# Opener.net
KiCad netlist of a schematic drawn in EAGLE
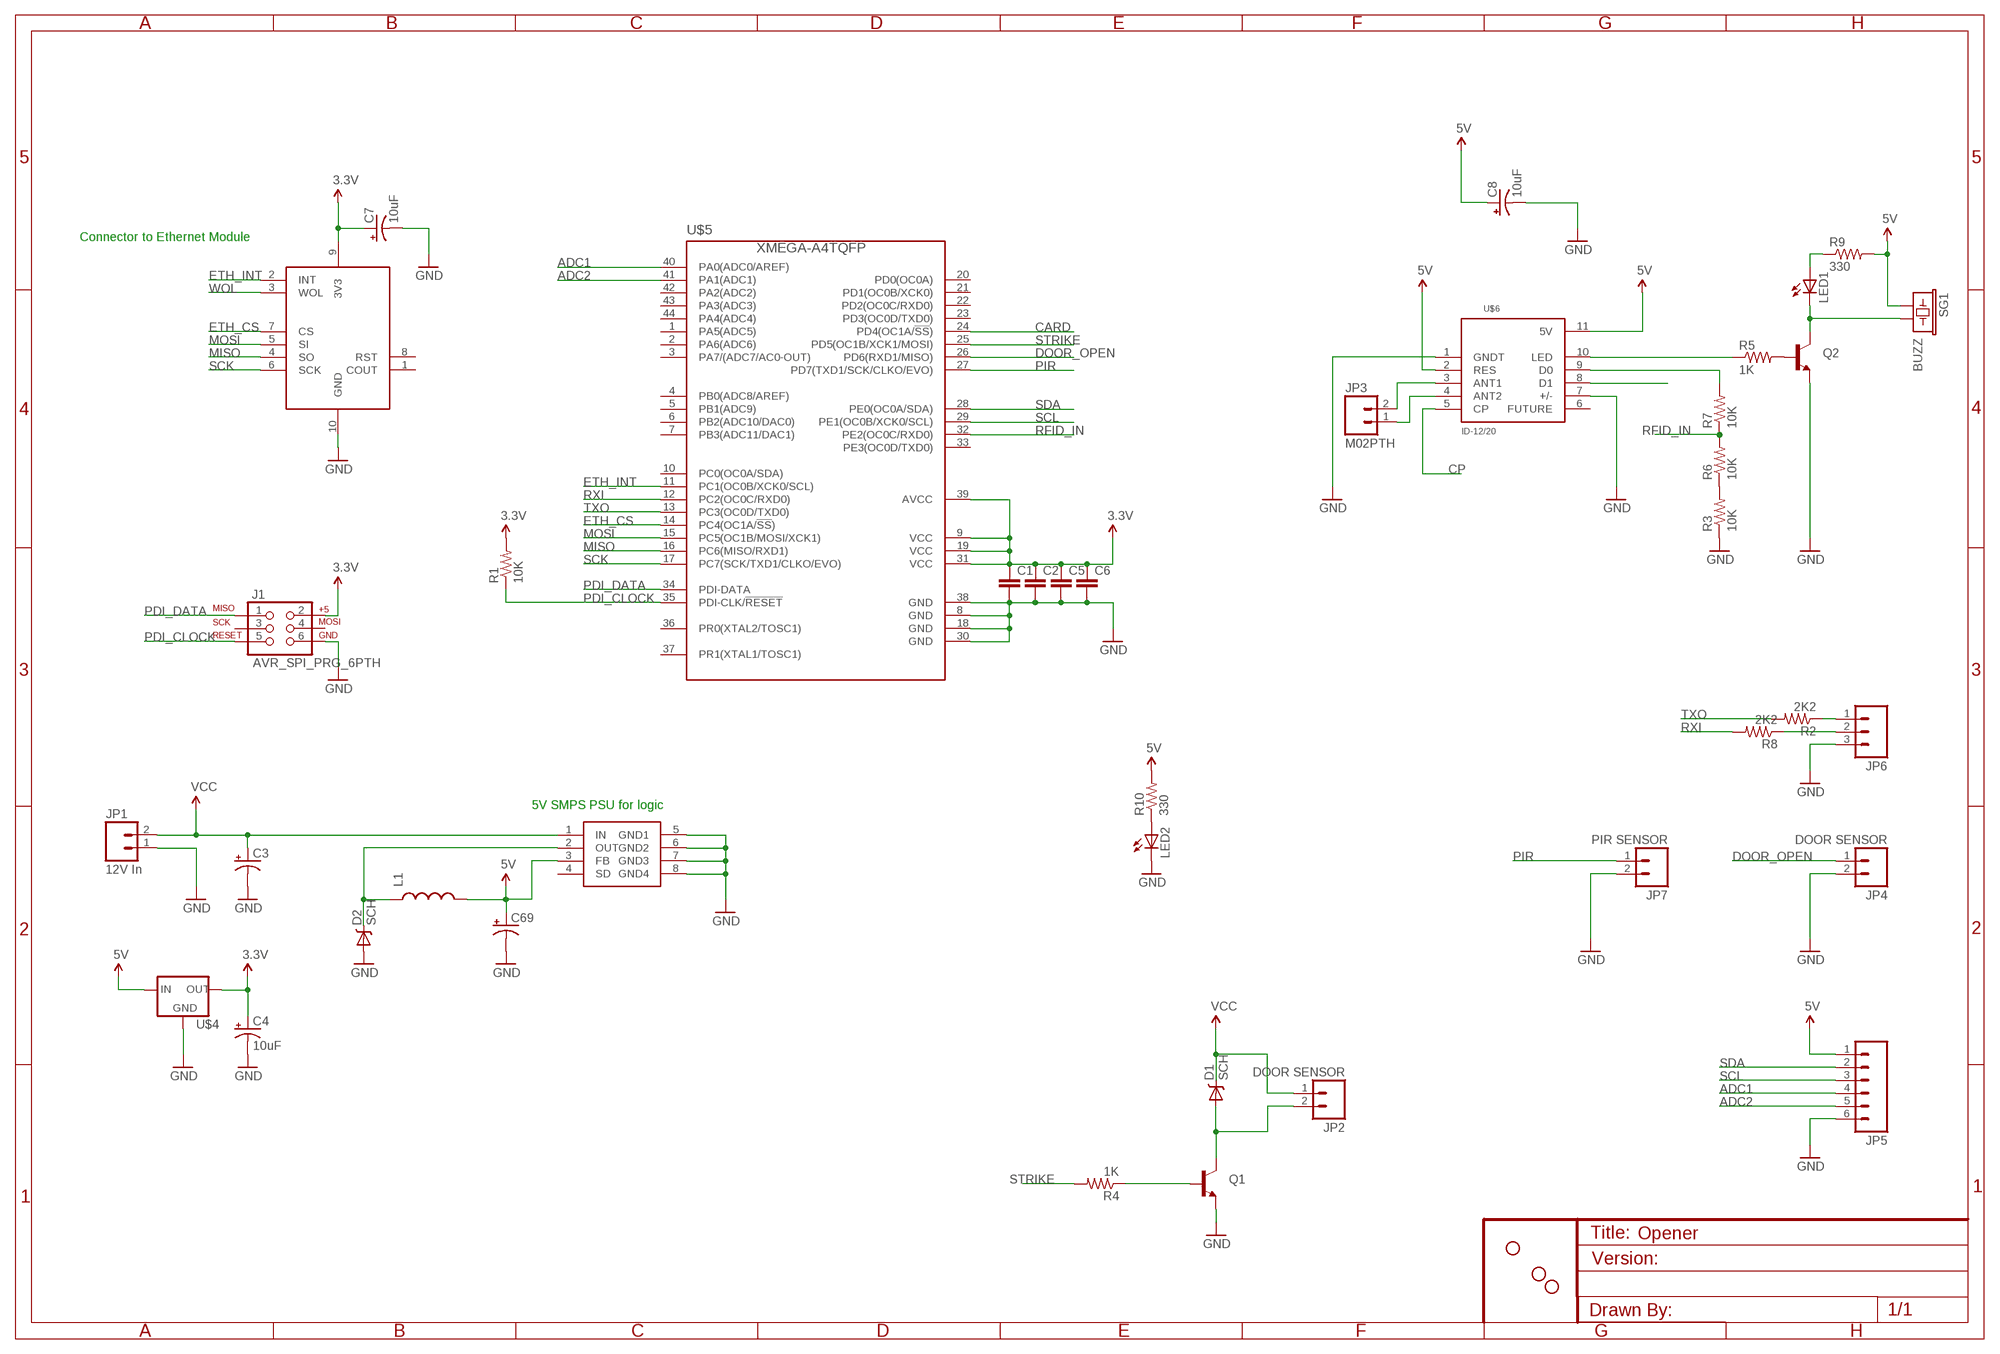
[diagram p0: schematic, sheet 1]

(export (version "E")
  (design (tool "Eeschema 10.0.6"))
  (components
    (comp (ref "C1")
      (value "CAP0603-CAP")
      (footprint "eagle-import:0603-CAP")
      (libsource (lib "eagle-import") (part "CAP0603-CAP"))
    )
    (comp (ref "C2")
      (value "CAP0603-CAP")
      (footprint "eagle-import:0603-CAP")
      (libsource (lib "eagle-import") (part "CAP0603-CAP"))
    )
    (comp (ref "C3")
      (value "CAP_POLPTH1")
      (footprint "eagle-import:CPOL-RADIAL-100UF-25V")
      (libsource (lib "eagle-import") (part "CAP_POLPTH1"))
    )
    (comp (ref "C4")
      (value "10uF")
      (footprint "eagle-import:EIA3216")
      (libsource (lib "eagle-import") (part "CAP_POL1206"))
    )
    (comp (ref "C5")
      (value "CAP0603-CAP")
      (footprint "eagle-import:0603-CAP")
      (libsource (lib "eagle-import") (part "CAP0603-CAP"))
    )
    (comp (ref "C6")
      (value "CAP0603-CAP")
      (footprint "eagle-import:0603-CAP")
      (libsource (lib "eagle-import") (part "CAP0603-CAP"))
    )
    (comp (ref "C7")
      (value "10uF")
      (footprint "eagle-import:EIA3216")
      (libsource (lib "eagle-import") (part "CAP_POL1206"))
    )
    (comp (ref "C8")
      (value "10uF")
      (footprint "eagle-import:EIA3216")
      (libsource (lib "eagle-import") (part "CAP_POL1206"))
    )
    (comp (ref "C69")
      (value "CAP_POLPTH1")
      (footprint "eagle-import:CPOL-RADIAL-100UF-25V")
      (libsource (lib "eagle-import") (part "CAP_POLPTH1"))
    )
    (comp (ref "D1")
      (value "SCH")
      (footprint "eagle-import:SMA-DIODE")
      (libsource (lib "eagle-import") (part "DIODE-SCHOTTKY_"))
    )
    (comp (ref "D2")
      (value "SCH")
      (footprint "eagle-import:SMA-DIODE")
      (libsource (lib "eagle-import") (part "DIODE-SCHOTTKY_"))
    )
    (comp (ref "J1")
      (value "AVR_SPI_PRG_6PTH")
      (footprint "eagle-import:2X3")
      (libsource (lib "eagle-import") (part "AVR_SPI_PRG_6PTH"))
    )
    (comp (ref "JP1")
      (value "12V In")
      (footprint "eagle-import:SCREWTERMINAL-3.5MM-2")
      (libsource (lib "eagle-import") (part "M023.5MM"))
    )
    (comp (ref "JP2")
      (value "DOOR SENSOR")
      (footprint "eagle-import:MOLEX-1X2")
      (libsource (lib "eagle-import") (part "M02POLAR"))
    )
    (comp (ref "JP3")
      (value "M02PTH")
      (footprint "eagle-import:1X02")
      (libsource (lib "eagle-import") (part "M02PTH"))
    )
    (comp (ref "JP4")
      (value "DOOR SENSOR")
      (footprint "eagle-import:MOLEX-1X2")
      (libsource (lib "eagle-import") (part "M02POLAR"))
    )
    (comp (ref "JP5")
      (value "M06SIP")
      (footprint "eagle-import:1X06")
      (libsource (lib "eagle-import") (part "M06SIP"))
    )
    (comp (ref "JP6")
      (value "M03PTH")
      (footprint "eagle-import:1X03")
      (libsource (lib "eagle-import") (part "M03PTH"))
    )
    (comp (ref "JP7")
      (value "PIR SENSOR")
      (footprint "eagle-import:MOLEX-1X2")
      (libsource (lib "eagle-import") (part "M02POLAR"))
    )
    (comp (ref "L1")
      (value "INDUCTOR1206H*")
      (footprint "eagle-import:INDUCTOR-1206")
      (libsource (lib "eagle-import") (part "INDUCTORH1206"))
    )
    (comp (ref "LED1")
      (value "LED-FKIT-1206")
      (footprint "eagle-import:FKIT-LED-1206")
      (libsource (lib "eagle-import") (part "LED-FKIT-1206"))
    )
    (comp (ref "LED2")
      (value "LED-FKIT-1206")
      (footprint "eagle-import:FKIT-LED-1206")
      (libsource (lib "eagle-import") (part "LED-FKIT-1206"))
    )
    (comp (ref "Q1")
      (value "TRANSISTOR_NPNTO92")
      (footprint "eagle-import:TO-92")
      (libsource (lib "eagle-import") (part "TRANSISTOR_NPNTO92"))
    )
    (comp (ref "Q2")
      (value "TRANSISTOR_NPNSOT23")
      (footprint "eagle-import:SOT23")
      (libsource (lib "eagle-import") (part "TRANSISTOR_NPNSOT23"))
    )
    (comp (ref "R1")
      (value "10K")
      (footprint "eagle-import:1206")
      (libsource (lib "eagle-import") (part "RESISTOR1206"))
    )
    (comp (ref "R2")
      (value "2K2")
      (footprint "eagle-import:1206")
      (libsource (lib "eagle-import") (part "RESISTOR1206"))
    )
    (comp (ref "R3")
      (value "10K")
      (footprint "eagle-import:1206")
      (libsource (lib "eagle-import") (part "RESISTOR1206"))
    )
    (comp (ref "R4")
      (value "1K")
      (footprint "eagle-import:1206")
      (libsource (lib "eagle-import") (part "RESISTOR1206"))
    )
    (comp (ref "R5")
      (value "1K")
      (footprint "eagle-import:1206")
      (libsource (lib "eagle-import") (part "RESISTOR1206"))
    )
    (comp (ref "R6")
      (value "10K")
      (footprint "eagle-import:1206")
      (libsource (lib "eagle-import") (part "RESISTOR1206"))
    )
    (comp (ref "R7")
      (value "10K")
      (footprint "eagle-import:1206")
      (libsource (lib "eagle-import") (part "RESISTOR1206"))
    )
    (comp (ref "R8")
      (value "2K2")
      (footprint "eagle-import:1206")
      (libsource (lib "eagle-import") (part "RESISTOR1206"))
    )
    (comp (ref "R9")
      (value "330")
      (footprint "eagle-import:1206")
      (libsource (lib "eagle-import") (part "RESISTOR1206"))
    )
    (comp (ref "R10")
      (value "330")
      (footprint "eagle-import:1206")
      (libsource (lib "eagle-import") (part "RESISTOR1206"))
    )
    (comp (ref "SG1")
      (value "BUZZ")
      (footprint "eagle-import:BUZZER-CCV")
      (libsource (lib "eagle-import") (part "BUZZERSMD2"))
    )
    (comp (ref "STANDOFF1")
      (value "STAND-OFF")
      (footprint "eagle-import:STAND-OFF")
      (libsource (lib "eagle-import") (part "STAND-OFF"))
    )
    (comp (ref "STANDOFF3")
      (value "STAND-OFF")
      (footprint "eagle-import:STAND-OFF")
      (libsource (lib "eagle-import") (part "STAND-OFF"))
    )
    (comp (ref "STANDOFF4")
      (value "STAND-OFF")
      (footprint "eagle-import:STAND-OFF")
      (libsource (lib "eagle-import") (part "STAND-OFF"))
    )
    (comp (ref "U$1")
      (value "ETHMODULE")
      (footprint "eagle-import:2X5")
      (libsource (lib "eagle-import") (part "ETHMODULE"))
    )
    (comp (ref "U$3")
      (value "AP1509-33")
      (footprint "eagle-import:SOIC-8")
      (libsource (lib "eagle-import") (part "AP1509-33"))
    )
    (comp (ref "U$4")
      (value "V_REG_MIC2920")
      (footprint "eagle-import:SOT223")
      (libsource (lib "eagle-import") (part "V_REG_MIC2920"))
    )
    (comp (ref "U$5")
      (value "XMEGA-A4TQFP")
      (footprint "eagle-import:TQFP44")
      (libsource (lib "eagle-import") (part "XMEGA-A4TQFP"))
    )
    (comp (ref "U$6")
      (value "ID-12/20")
      (footprint "eagle-import:ID-12")
      (libsource (lib "eagle-import") (part "ID-12/20"))
    )
  )
  (nets
    (net (code "1") (name "/ADC1") (class "Default")
      (node (ref "JP5") (pin "4") (pinfunction "4_4") (pintype "passive"))
      (node (ref "U$5") (pin "40") (pinfunction "PA0(ADC0/AREF)_40") (pintype "bidirectional"))
    )
    (net (code "2") (name "/ADC2") (class "Default")
      (node (ref "JP5") (pin "5") (pinfunction "5_5") (pintype "passive"))
      (node (ref "U$5") (pin "41") (pinfunction "PA1(ADC1)_41") (pintype "bidirectional"))
    )
    (net (code "3") (name "/CARD") (class "Default")
      (node (ref "U$5") (pin "24") (pinfunction "PD4(OC1A/~{SS})_24") (pintype "bidirectional"))
    )
    (net (code "4") (name "/COUT") (class "Default")
      (node (ref "U$1") (pin "1") (pinfunction "COUT_1") (pintype "power_in"))
    )
    (net (code "5") (name "/CP") (class "Default")
      (node (ref "U$6") (pin "5") (pinfunction "CP_5") (pintype "bidirectional"))
    )
    (net (code "6") (name "/DOOR_OPEN") (class "Default")
      (node (ref "JP4") (pin "1") (pinfunction "1_1") (pintype "passive"))
      (node (ref "U$5") (pin "26") (pinfunction "PD6(RXD1/MISO)_26") (pintype "bidirectional"))
    )
    (net (code "7") (name "/ETH_CS") (class "Default")
      (node (ref "U$1") (pin "7") (pinfunction "CS_7") (pintype "power_in"))
      (node (ref "U$5") (pin "14") (pinfunction "PC4(OC1A/~{SS})_14") (pintype "bidirectional"))
    )
    (net (code "8") (name "/ETH_INT") (class "Default")
      (node (ref "U$1") (pin "2") (pinfunction "INT_2") (pintype "power_in"))
      (node (ref "U$5") (pin "11") (pinfunction "PC1(OC0B/XCK0/SCL)_11") (pintype "bidirectional"))
    )
    (net (code "9") (name "/MISO") (class "Default")
      (node (ref "U$1") (pin "4") (pinfunction "SO_4") (pintype "power_in"))
      (node (ref "U$5") (pin "16") (pinfunction "PC6(MISO/RXD1)_16") (pintype "bidirectional"))
    )
    (net (code "10") (name "/MOSI") (class "Default")
      (node (ref "U$1") (pin "5") (pinfunction "SI_5") (pintype "power_in"))
      (node (ref "U$5") (pin "15") (pinfunction "PC5(OC1B/MOSI/XCK1)_15") (pintype "bidirectional"))
    )
    (net (code "11") (name "/PDI_CLOCK") (class "Default")
      (node (ref "J1") (pin "5") (pinfunction "5_5") (pintype "passive"))
      (node (ref "R1") (pin "1") (pinfunction "1_1") (pintype "passive"))
      (node (ref "U$5") (pin "35") (pinfunction "PDI-CLK/~{RESET}_35") (pintype "input"))
    )
    (net (code "12") (name "/PDI_DATA") (class "Default")
      (node (ref "J1") (pin "1") (pinfunction "1_1") (pintype "passive"))
      (node (ref "U$5") (pin "34") (pinfunction "PDI-DATA_34") (pintype "bidirectional"))
    )
    (net (code "13") (name "/PIR") (class "Default")
      (node (ref "JP7") (pin "1") (pinfunction "1_1") (pintype "passive"))
      (node (ref "U$5") (pin "27") (pinfunction "PD7(TXD1/SCK/CLKO/EVO)_27") (pintype "bidirectional"))
    )
    (net (code "14") (name "/RFID_IN") (class "Default")
      (node (ref "R6") (pin "2") (pinfunction "2_2") (pintype "passive"))
      (node (ref "R7") (pin "1") (pinfunction "1_1") (pintype "passive"))
      (node (ref "U$5") (pin "32") (pinfunction "PE2(OC0C/RXD0)_32") (pintype "bidirectional"))
    )
    (net (code "15") (name "/RST") (class "Default")
      (node (ref "U$1") (pin "8") (pinfunction "RST_8") (pintype "power_in"))
    )
    (net (code "16") (name "/RXI") (class "Default")
      (node (ref "R8") (pin "2") (pinfunction "2_2") (pintype "passive"))
      (node (ref "U$5") (pin "12") (pinfunction "PC2(OC0C/RXD0)_12") (pintype "bidirectional"))
    )
    (net (code "17") (name "/SCK") (class "Default")
      (node (ref "U$1") (pin "6") (pinfunction "SCK_6") (pintype "power_in"))
      (node (ref "U$5") (pin "17") (pinfunction "PC7(SCK/TXD1/CLKO/EVO)_17") (pintype "bidirectional"))
    )
    (net (code "18") (name "/SCL") (class "Default")
      (node (ref "JP5") (pin "3") (pinfunction "3_3") (pintype "passive"))
      (node (ref "U$5") (pin "29") (pinfunction "PE1(OC0B/XCK0/SCL)_29") (pintype "bidirectional"))
    )
    (net (code "19") (name "/SDA") (class "Default")
      (node (ref "JP5") (pin "2") (pinfunction "2_2") (pintype "passive"))
      (node (ref "U$5") (pin "28") (pinfunction "PE0(OC0A/SDA)_28") (pintype "bidirectional"))
    )
    (net (code "20") (name "/STRIKE") (class "Default")
      (node (ref "R4") (pin "2") (pinfunction "2_2") (pintype "passive"))
      (node (ref "U$5") (pin "25") (pinfunction "PD5(OC1B/XCK1/MOSI)_25") (pintype "bidirectional"))
    )
    (net (code "21") (name "/TXO") (class "Default")
      (node (ref "R2") (pin "2") (pinfunction "2_2") (pintype "passive"))
      (node (ref "U$5") (pin "13") (pinfunction "PC3(OC0D/TXD0)_13") (pintype "bidirectional"))
    )
    (net (code "22") (name "/WOL") (class "Default")
      (node (ref "U$1") (pin "3") (pinfunction "WOL_3") (pintype "power_in"))
    )
    (net (code "23") (name "3.3V") (class "Default")
      (node (ref "C1") (pin "1") (pinfunction "1_1") (pintype "passive"))
      (node (ref "C2") (pin "1") (pinfunction "1_1") (pintype "passive"))
      (node (ref "C4") (pin "A") (pinfunction "+_A") (pintype "passive"))
      (node (ref "C5") (pin "1") (pinfunction "1_1") (pintype "passive"))
      (node (ref "C6") (pin "1") (pinfunction "1_1") (pintype "passive"))
      (node (ref "C7") (pin "A") (pinfunction "+_A") (pintype "passive"))
      (node (ref "J1") (pin "2") (pinfunction "2_2") (pintype "passive"))
      (node (ref "R1") (pin "2") (pinfunction "2_2") (pintype "passive"))
      (node (ref "U$1") (pin "9") (pinfunction "3V3_9") (pintype "power_in"))
      (node (ref "U$4") (pin "3") (pinfunction "OUT_3") (pintype "output"))
      (node (ref "U$5") (pin "19") (pinfunction "VCC_19") (pintype "power_in"))
      (node (ref "U$5") (pin "31") (pinfunction "VCC_31") (pintype "power_in"))
      (node (ref "U$5") (pin "39") (pinfunction "AVCC_39") (pintype "power_in"))
      (node (ref "U$5") (pin "9") (pinfunction "VCC_9") (pintype "power_in"))
    )
    (net (code "24") (name "5V") (class "Default")
      (node (ref "C69") (pin "1") (pinfunction "+_1") (pintype "passive"))
      (node (ref "C8") (pin "A") (pinfunction "+_A") (pintype "passive"))
      (node (ref "JP5") (pin "1") (pinfunction "1_1") (pintype "passive"))
      (node (ref "L1") (pin "P$2") (pinfunction "2_P$2") (pintype "passive"))
      (node (ref "R10") (pin "2") (pinfunction "2_2") (pintype "passive"))
      (node (ref "R9") (pin "2") (pinfunction "2_2") (pintype "passive"))
      (node (ref "SG1") (pin "+") (pinfunction "1_+") (pintype "passive"))
      (node (ref "U$3") (pin "3") (pinfunction "FB_3") (pintype "bidirectional"))
      (node (ref "U$4") (pin "1") (pinfunction "IN_1") (pintype "input"))
      (node (ref "U$6") (pin "11") (pinfunction "5V_11") (pintype "bidirectional"))
      (node (ref "U$6") (pin "2") (pinfunction "RES_2") (pintype "bidirectional"))
    )
    (net (code "25") (name "GND") (class "Default")
      (node (ref "C1") (pin "2") (pinfunction "2_2") (pintype "passive"))
      (node (ref "C2") (pin "2") (pinfunction "2_2") (pintype "passive"))
      (node (ref "C3") (pin "2") (pinfunction "-_2") (pintype "passive"))
      (node (ref "C4") (pin "C") (pinfunction "-_C") (pintype "passive"))
      (node (ref "C5") (pin "2") (pinfunction "2_2") (pintype "passive"))
      (node (ref "C6") (pin "2") (pinfunction "2_2") (pintype "passive"))
      (node (ref "C69") (pin "2") (pinfunction "-_2") (pintype "passive"))
      (node (ref "C7") (pin "C") (pinfunction "-_C") (pintype "passive"))
      (node (ref "C8") (pin "C") (pinfunction "-_C") (pintype "passive"))
      (node (ref "D2") (pin "A") (pinfunction "A_A") (pintype "passive"))
      (node (ref "J1") (pin "6") (pinfunction "6_6") (pintype "passive"))
      (node (ref "JP1") (pin "1") (pinfunction "1_1") (pintype "passive"))
      (node (ref "JP4") (pin "2") (pinfunction "2_2") (pintype "passive"))
      (node (ref "JP5") (pin "6") (pinfunction "6_6") (pintype "passive"))
      (node (ref "JP6") (pin "3") (pinfunction "3_3") (pintype "passive"))
      (node (ref "JP7") (pin "2") (pinfunction "2_2") (pintype "passive"))
      (node (ref "LED2") (pin "C") (pinfunction "C_C") (pintype "passive"))
      (node (ref "Q1") (pin "1") (pinfunction "E_1") (pintype "passive"))
      (node (ref "Q2") (pin "2") (pinfunction "E_2") (pintype "passive"))
      (node (ref "R3") (pin "1") (pinfunction "1_1") (pintype "passive"))
      (node (ref "U$1") (pin "10") (pinfunction "GND_10") (pintype "power_in"))
      (node (ref "U$3") (pin "5") (pinfunction "GND1_5") (pintype "bidirectional"))
      (node (ref "U$3") (pin "6") (pinfunction "GND2_6") (pintype "bidirectional"))
      (node (ref "U$3") (pin "7") (pinfunction "GND3_7") (pintype "bidirectional"))
      (node (ref "U$3") (pin "8") (pinfunction "GND4_8") (pintype "bidirectional"))
      (node (ref "U$4") (pin "2") (pinfunction "GND_2") (pintype "input"))
      (node (ref "U$5") (pin "18") (pinfunction "GND_18") (pintype "power_in"))
      (node (ref "U$5") (pin "30") (pinfunction "GND_30") (pintype "power_in"))
      (node (ref "U$5") (pin "38") (pinfunction "GND_38") (pintype "power_in"))
      (node (ref "U$5") (pin "8") (pinfunction "GND_8") (pintype "power_in"))
      (node (ref "U$6") (pin "1") (pinfunction "GNDT_1") (pintype "bidirectional"))
      (node (ref "U$6") (pin "7") (pinfunction "+/-_7") (pintype "bidirectional"))
    )
    (net (code "26") (name "Net-(JP6-Pad1)") (class "Default")
      (node (ref "JP6") (pin "1") (pinfunction "1_1") (pintype "passive"))
      (node (ref "R2") (pin "1") (pinfunction "1_1") (pintype "passive"))
    )
    (net (code "27") (name "Net-(JP6-Pad2)") (class "Default")
      (node (ref "JP6") (pin "2") (pinfunction "2_2") (pintype "passive"))
      (node (ref "R8") (pin "1") (pinfunction "1_1") (pintype "passive"))
    )
    (net (code "28") (name "Net-(L1-1)") (class "Default")
      (node (ref "D2") (pin "C") (pinfunction "C_C") (pintype "passive"))
      (node (ref "L1") (pin "P$1") (pinfunction "1_P$1") (pintype "passive"))
      (node (ref "U$3") (pin "2") (pinfunction "OUT_2") (pintype "bidirectional"))
    )
    (net (code "29") (name "Net-(LED1-PadA)") (class "Default")
      (node (ref "LED1") (pin "A") (pinfunction "A_A") (pintype "passive"))
      (node (ref "R9") (pin "1") (pinfunction "1_1") (pintype "passive"))
    )
    (net (code "30") (name "Net-(LED2-PadA)") (class "Default")
      (node (ref "LED2") (pin "A") (pinfunction "A_A") (pintype "passive"))
      (node (ref "R10") (pin "1") (pinfunction "1_1") (pintype "passive"))
    )
    (net (code "31") (name "Net-(Q1-B)") (class "Default")
      (node (ref "Q1") (pin "2") (pinfunction "B_2") (pintype "passive"))
      (node (ref "R4") (pin "1") (pinfunction "1_1") (pintype "passive"))
    )
    (net (code "32") (name "Net-(Q1-C)") (class "Default")
      (node (ref "D1") (pin "A") (pinfunction "A_A") (pintype "passive"))
      (node (ref "JP2") (pin "2") (pinfunction "2_2") (pintype "passive"))
      (node (ref "Q1") (pin "3") (pinfunction "C_3") (pintype "passive"))
    )
    (net (code "33") (name "Net-(Q2-B)") (class "Default")
      (node (ref "Q2") (pin "1") (pinfunction "B_1") (pintype "passive"))
      (node (ref "R5") (pin "2") (pinfunction "2_2") (pintype "passive"))
    )
    (net (code "34") (name "Net-(Q2-C)") (class "Default")
      (node (ref "LED1") (pin "C") (pinfunction "C_C") (pintype "passive"))
      (node (ref "Q2") (pin "3") (pinfunction "C_3") (pintype "passive"))
      (node (ref "SG1") (pin "-") (pinfunction "2_-") (pintype "passive"))
    )
    (net (code "35") (name "Net-(R3-Pad2)") (class "Default")
      (node (ref "R3") (pin "2") (pinfunction "2_2") (pintype "passive"))
      (node (ref "R6") (pin "1") (pinfunction "1_1") (pintype "passive"))
    )
    (net (code "36") (name "Net-(U$6-ANT1)") (class "Default")
      (node (ref "JP3") (pin "2") (pinfunction "2_2") (pintype "passive"))
      (node (ref "U$6") (pin "3") (pinfunction "ANT1_3") (pintype "bidirectional"))
    )
    (net (code "37") (name "Net-(U$6-ANT2)") (class "Default")
      (node (ref "JP3") (pin "1") (pinfunction "1_1") (pintype "passive"))
      (node (ref "U$6") (pin "4") (pinfunction "ANT2_4") (pintype "bidirectional"))
    )
    (net (code "38") (name "Net-(U$6-D0)") (class "Default")
      (node (ref "R7") (pin "2") (pinfunction "2_2") (pintype "passive"))
      (node (ref "U$6") (pin "9") (pinfunction "D0_9") (pintype "bidirectional"))
    )
    (net (code "39") (name "Net-(U$6-LED)") (class "Default")
      (node (ref "R5") (pin "1") (pinfunction "1_1") (pintype "passive"))
      (node (ref "U$6") (pin "10") (pinfunction "LED_10") (pintype "bidirectional"))
    )
    (net (code "40") (name "VCC") (class "Default")
      (node (ref "C3") (pin "1") (pinfunction "+_1") (pintype "passive"))
      (node (ref "D1") (pin "C") (pinfunction "C_C") (pintype "passive"))
      (node (ref "JP1") (pin "2") (pinfunction "2_2") (pintype "passive"))
      (node (ref "JP2") (pin "1") (pinfunction "1_1") (pintype "passive"))
      (node (ref "U$3") (pin "1") (pinfunction "IN_1") (pintype "bidirectional"))
    )
    (net (code "41") (name "unconnected-(J1-Pad3)") (class "Default")
      (node (ref "J1") (pin "3") (pinfunction "3_3") (pintype "passive"))
    )
    (net (code "42") (name "unconnected-(J1-Pad4)") (class "Default")
      (node (ref "J1") (pin "4") (pinfunction "4_4") (pintype "passive"))
    )
    (net (code "43") (name "unconnected-(U$3-SD-Pad4)") (class "Default")
      (node (ref "U$3") (pin "4") (pinfunction "SD_4") (pintype "bidirectional"))
    )
    (net (code "44") (name "unconnected-(U$5-PA2(ADC2)-Pad42)") (class "Default")
      (node (ref "U$5") (pin "42") (pinfunction "PA2(ADC2)_42") (pintype "bidirectional"))
    )
    (net (code "45") (name "unconnected-(U$5-PA3(ADC3)-Pad43)") (class "Default")
      (node (ref "U$5") (pin "43") (pinfunction "PA3(ADC3)_43") (pintype "bidirectional"))
    )
    (net (code "46") (name "unconnected-(U$5-PA4(ADC4)-Pad44)") (class "Default")
      (node (ref "U$5") (pin "44") (pinfunction "PA4(ADC4)_44") (pintype "bidirectional"))
    )
    (net (code "47") (name "unconnected-(U$5-PA5(ADC5)-Pad1)") (class "Default")
      (node (ref "U$5") (pin "1") (pinfunction "PA5(ADC5)_1") (pintype "bidirectional"))
    )
    (net (code "48") (name "unconnected-(U$5-PA6(ADC6)-Pad2)") (class "Default")
      (node (ref "U$5") (pin "2") (pinfunction "PA6(ADC6)_2") (pintype "bidirectional"))
    )
    (net (code "49") (name "unconnected-(U$5-PA7{slash}(ADC7{slash}AC0-OUT)-Pad3)") (class "Default")
      (node (ref "U$5") (pin "3") (pinfunction "PA7/(ADC7/AC0-OUT)_3") (pintype "bidirectional"))
    )
    (net (code "50") (name "unconnected-(U$5-PB0(ADC8{slash}AREF)-Pad4)") (class "Default")
      (node (ref "U$5") (pin "4") (pinfunction "PB0(ADC8/AREF)_4") (pintype "bidirectional"))
    )
    (net (code "51") (name "unconnected-(U$5-PB1(ADC9)-Pad5)") (class "Default")
      (node (ref "U$5") (pin "5") (pinfunction "PB1(ADC9)_5") (pintype "bidirectional"))
    )
    (net (code "52") (name "unconnected-(U$5-PB2(ADC10{slash}DAC0)-Pad6)") (class "Default")
      (node (ref "U$5") (pin "6") (pinfunction "PB2(ADC10/DAC0)_6") (pintype "bidirectional"))
    )
    (net (code "53") (name "unconnected-(U$5-PB3(ADC11{slash}DAC1)-Pad7)") (class "Default")
      (node (ref "U$5") (pin "7") (pinfunction "PB3(ADC11/DAC1)_7") (pintype "bidirectional"))
    )
    (net (code "54") (name "unconnected-(U$5-PC0(OC0A{slash}SDA)-Pad10)") (class "Default")
      (node (ref "U$5") (pin "10") (pinfunction "PC0(OC0A/SDA)_10") (pintype "bidirectional"))
    )
    (net (code "55") (name "unconnected-(U$5-PD0(OC0A)-Pad20)") (class "Default")
      (node (ref "U$5") (pin "20") (pinfunction "PD0(OC0A)_20") (pintype "bidirectional"))
    )
    (net (code "56") (name "unconnected-(U$5-PD1(OC0B{slash}XCK0)-Pad21)") (class "Default")
      (node (ref "U$5") (pin "21") (pinfunction "PD1(OC0B/XCK0)_21") (pintype "bidirectional"))
    )
    (net (code "57") (name "unconnected-(U$5-PD2(OC0C{slash}RXD0)-Pad22)") (class "Default")
      (node (ref "U$5") (pin "22") (pinfunction "PD2(OC0C/RXD0)_22") (pintype "bidirectional"))
    )
    (net (code "58") (name "unconnected-(U$5-PD3(OC0D{slash}TXD0)-Pad23)") (class "Default")
      (node (ref "U$5") (pin "23") (pinfunction "PD3(OC0D/TXD0)_23") (pintype "bidirectional"))
    )
    (net (code "59") (name "unconnected-(U$5-PE3(OC0D{slash}TXD0)-Pad33)") (class "Default")
      (node (ref "U$5") (pin "33") (pinfunction "PE3(OC0D/TXD0)_33") (pintype "bidirectional"))
    )
    (net (code "60") (name "unconnected-(U$5-PR0(XTAL2{slash}TOSC1)-Pad36)") (class "Default")
      (node (ref "U$5") (pin "36") (pinfunction "PR0(XTAL2/TOSC1)_36") (pintype "bidirectional"))
    )
    (net (code "61") (name "unconnected-(U$5-PR1(XTAL1{slash}TOSC1)-Pad37)") (class "Default")
      (node (ref "U$5") (pin "37") (pinfunction "PR1(XTAL1/TOSC1)_37") (pintype "bidirectional"))
    )
    (net (code "62") (name "unconnected-(U$6-D1-Pad8)") (class "Default")
      (node (ref "U$6") (pin "8") (pinfunction "D1_8") (pintype "bidirectional"))
    )
    (net (code "63") (name "unconnected-(U$6-FUTURE-Pad6)") (class "Default")
      (node (ref "U$6") (pin "6") (pinfunction "FUTURE_6") (pintype "bidirectional"))
    )
  )
)
